# Snippet_of_Dev.net
KiCad netlist of a schematic drawn in Altium Designer
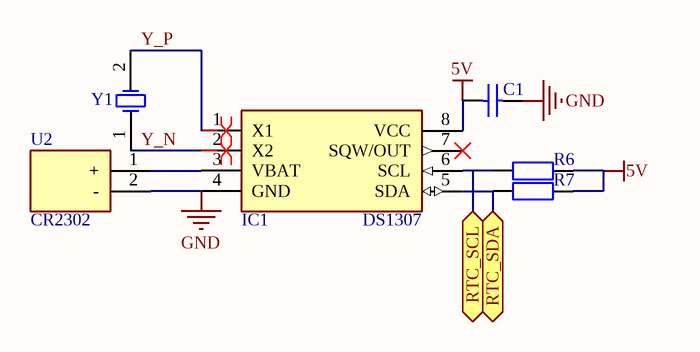
[diagram p0: Snippet of Dev.SchDoc]

(export (version "E")
  (design (tool "Eeschema 10.0.6"))
  (components
    (comp (ref "C1")
      (value "100nF")
      (footprint "CAP-0603")
      (description "贴片电容")
      (libsource (lib "Power_Lib_Altium") (part "CAP"))
    )
    (comp (ref "IC1")
      (value "DS1307")
      (footprint "SOIC_8")
      (description "Integrated Circuit")
      (fields
        (field (name "MANUFACTURER_PART_NUMBER") "DS1307+")
        (field (name "MOUSER PART NUMBER") "700-DS1307")
      )
      (libsource (lib "Power_Lib_Altium") (part "DS1307"))
    )
    (comp (ref "R6")
      (value "4.7K")
      (footprint "R-0603")
      (description "贴片电阻")
      (libsource (lib "Power_Lib_Altium") (part "RES"))
    )
    (comp (ref "R7")
      (value "4.7K")
      (footprint "R-0603")
      (description "贴片电阻")
      (libsource (lib "Power_Lib_Altium") (part "RES"))
    )
    (comp (ref "U2")
      (value "CR2302")
      (footprint "CR2032-1")
      (description "锂电池")
      (fields (field (name "MANUFACTURER_PART_NUMBER") "1026") (field (name "MOUSER PART NUMBER") "534-1026"))
      (libsource (lib "Power_Lib_Altium") (part "BAT"))
    )
    (comp (ref "Y1")
      (value "32.768KHz ±20ppm 12.5pF")
      (footprint "SMD-3215_2P FC - 135")
      (description "无源晶振")
      (libsource (lib "Power_Lib_Altium") (part "Crystal"))
    )
  )
  (nets
    (net (code "1") (name "/RTC_SCL") (class "Default")
      (node (ref "IC1") (pin "6") (pinfunction "SCL_6") (pintype "input"))
      (node (ref "R6") (pin "1") (pinfunction "1_1") (pintype "passive"))
    )
    (net (code "2") (name "/RTC_SDA") (class "Default")
      (node (ref "IC1") (pin "5") (pinfunction "SDA_5") (pintype "bidirectional"))
      (node (ref "R7") (pin "1") (pinfunction "1_1") (pintype "passive"))
    )
    (net (code "3") (name "/Y_N") (class "Default")
      (node (ref "IC1") (pin "2") (pinfunction "X2_2") (pintype "passive"))
      (node (ref "Y1") (pin "1") (pinfunction "OSC1_1") (pintype "passive"))
    )
    (net (code "4") (name "/Y_P") (class "Default")
      (node (ref "IC1") (pin "1") (pinfunction "X1_1") (pintype "passive"))
      (node (ref "Y1") (pin "2") (pinfunction "OSC2_2") (pintype "passive"))
    )
    (net (code "5") (name "5V") (class "Default")
      (node (ref "C1") (pin "1") (pinfunction "1_1") (pintype "passive"))
      (node (ref "IC1") (pin "8") (pinfunction "VCC_8") (pintype "power_in"))
      (node (ref "R6") (pin "2") (pinfunction "2_2") (pintype "passive"))
      (node (ref "R7") (pin "2") (pinfunction "2_2") (pintype "passive"))
    )
    (net (code "6") (name "GND") (class "Default")
      (node (ref "C1") (pin "2") (pinfunction "2_2") (pintype "passive"))
      (node (ref "IC1") (pin "4") (pinfunction "GND_4") (pintype "power_in"))
      (node (ref "U2") (pin "2") (pinfunction "-_2") (pintype "passive"))
    )
    (net (code "7") (name "Net-(IC1-VBAT)") (class "Default")
      (node (ref "IC1") (pin "3") (pinfunction "VBAT_3") (pintype "power_in"))
      (node (ref "U2") (pin "1") (pinfunction "+_1") (pintype "passive"))
    )
    (net (code "8") (name "unconnected-(IC1-SQW{slash}OUT-Pad7)") (class "Default")
      (node (ref "IC1") (pin "7") (pinfunction "SQW/OUT_7") (pintype "output+no_connect"))
    )
  )
)
